# CH32V006-WUI-R1.net
KiCad netlist of a schematic drawn in Altium Designer
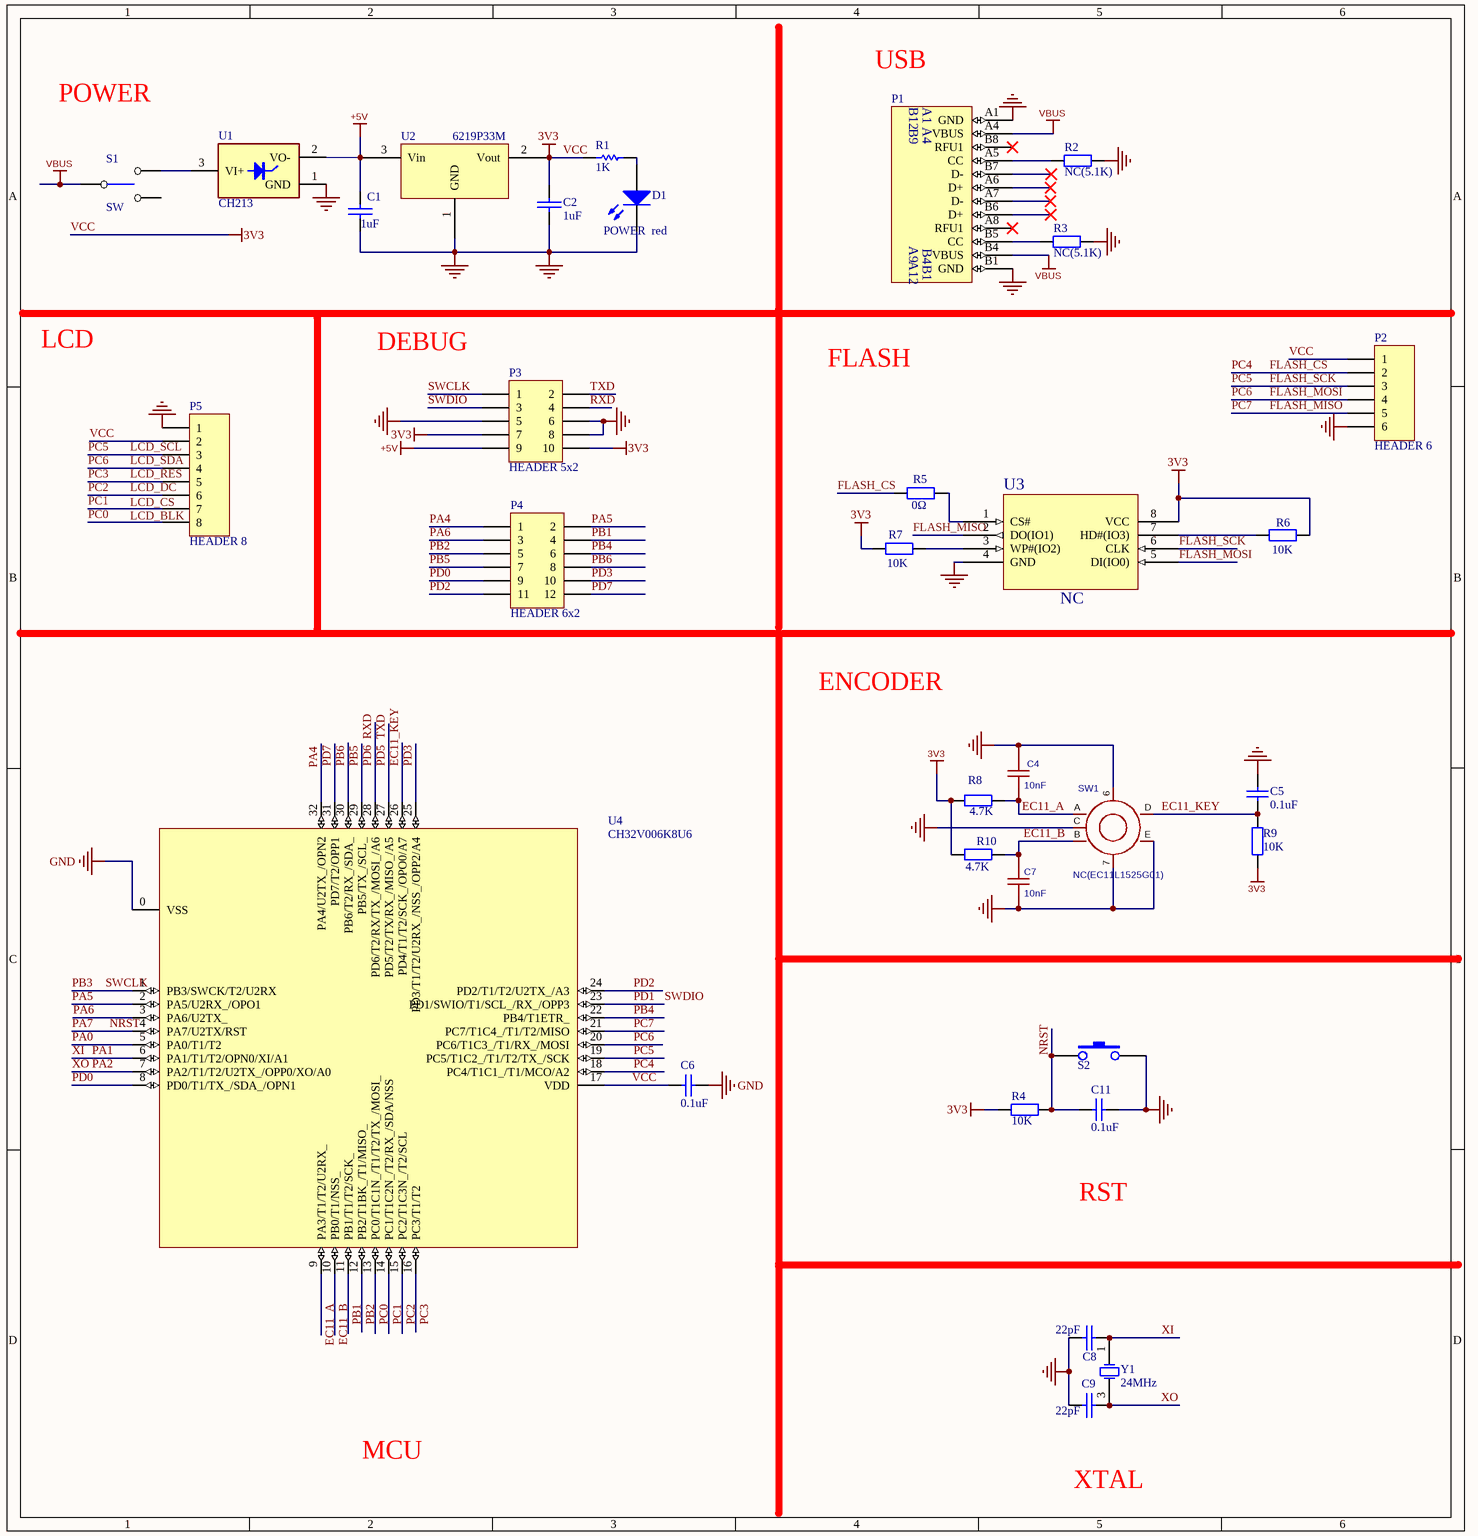
[diagram p0: CH32V006-WUI-R1.SchDoc]

(export (version "E")
  (design (tool "Eeschema 10.0.6"))
  (components
    (comp (ref "C1")
      (value "1uF")
      (footprint "0402_C")
      (description "Capacitor")
      (libsource (lib "*") (part "CAP"))
    )
    (comp (ref "C2")
      (value "1uF")
      (footprint "0402_C")
      (description "Capacitor")
      (libsource (lib "*") (part "CAP"))
    )
    (comp (ref "C4")
      (value "10nF")
      (footprint "0402_C")
      (libsource (lib "altium-import") (part "root_1_CAP_0603_"))
    )
    (comp (ref "C5")
      (value "0.1uF")
      (footprint "0402_C")
      (description "Capacitor")
      (fields (field (name "PUBLISHER") "Altium Limited"))
      (libsource (lib "*") (part "Cap"))
    )
    (comp (ref "C6")
      (value "0.1uF")
      (footprint "0402_C")
      (description "Capacitor")
      (fields (field (name "PUBLISHER") "Altium Limited"))
      (libsource (lib "*") (part "Cap"))
    )
    (comp (ref "C7")
      (value "10nF")
      (footprint "0402_C")
      (libsource (lib "altium-import") (part "root_3_CAP_0603_"))
    )
    (comp (ref "C8")
      (value "22pF")
      (footprint "0402_C")
      (description "Capacitor")
      (libsource (lib "*") (part "CAP"))
    )
    (comp (ref "C9")
      (value "22pF")
      (footprint "0402_C")
      (description "Capacitor")
      (libsource (lib "*") (part "CAP"))
    )
    (comp (ref "C11")
      (value "0.1uF")
      (footprint "0402_C")
      (description "Capacitor")
      (fields (field (name "PUBLISHER") "Altium Limited"))
      (libsource (lib "*") (part "Cap"))
    )
    (comp (ref "D1")
      (value "POWER  red")
      (footprint "0603+")
      (description "Typical INFRARED GaAs LED")
      (fields (field (name "PUBLISHER") "Altium Limited"))
      (libsource (lib "*") (part "LED0"))
    )
    (comp (ref "P1")
      (value "TYPE-C")
      (footprint "TYPE-C-Receptacle-2.0")
      (libsource (lib "*") (part "TYPE-C1"))
    )
    (comp (ref "P2")
      (value "HEADER 6")
      (footprint "SIP6-2.54mm")
      (description "Header, 6-Pin")
      (libsource (lib "wch_sch_others") (part "HEADER 6"))
    )
    (comp (ref "P3")
      (value "HEADER 5x2")
      (footprint "MYPCB:IDC10-2.54mm")
      (description "Header, 5-Pin, Dual row")
      (libsource (lib "wch_sch_others") (part "HEADER 5x2"))
    )
    (comp (ref "P4")
      (value "HEADER 6x2")
      (footprint "MYPCB:IDC12-2.54mm")
      (description "Header, 6-Pin, Dual row")
      (libsource (lib "wch_sch_others") (part "HEADER 6x2"))
    )
    (comp (ref "P5")
      (value "HEADER 8")
      (footprint "SIP8-2.54mm")
      (description "Header, 8-Pin")
      (libsource (lib "wch_sch_others") (part "HEADER 8"))
    )
    (comp (ref "R1")
      (value "1K")
      (footprint "0402")
      (description "Semiconductor Resistor")
      (fields (field (name "PUBLISHER") "Altium Limited"))
      (libsource (lib "*") (part "Res Semi"))
    )
    (comp (ref "R2")
      (value "NC(5.1K)")
      (footprint "0402")
      (description "Resistor")
      (libsource (lib "Miscellaneous Devices") (part "Res2"))
    )
    (comp (ref "R3")
      (value "NC(5.1K)")
      (footprint "0402")
      (description "Resistor")
      (libsource (lib "Miscellaneous Devices") (part "Res2"))
    )
    (comp (ref "R4")
      (value "10K")
      (footprint "0402")
      (description "Resistor")
      (fields (field (name "PUBLISHER") "Altium Limited"))
      (libsource (lib "") (part "Res2_1"))
    )
    (comp (ref "R5")
      (value "0Ω")
      (footprint "0402")
      (description "Resistor")
      (fields (field (name "PUBLISHER") "Altium Limited"))
      (libsource (lib "*") (part "Res2"))
    )
    (comp (ref "R6")
      (value "10K")
      (footprint "0402")
      (description "Resistor")
      (fields (field (name "PUBLISHER") "Altium Limited"))
      (libsource (lib "*") (part "Res2"))
    )
    (comp (ref "R7")
      (value "10K")
      (footprint "0402")
      (description "Resistor")
      (fields (field (name "PUBLISHER") "Altium Limited"))
      (libsource (lib "*") (part "Res2"))
    )
    (comp (ref "R8")
      (value "4.7K")
      (footprint "0402")
      (description "Resistor")
      (fields (field (name "PUBLISHER") "Altium Limited"))
      (libsource (lib "*") (part "Res2"))
    )
    (comp (ref "R9")
      (value "10K")
      (footprint "0402")
      (description "Resistor")
      (fields (field (name "PUBLISHER") "Altium Limited"))
      (libsource (lib "") (part "Res2_2"))
    )
    (comp (ref "R10")
      (value "4.7K")
      (footprint "0402")
      (description "Resistor")
      (fields (field (name "PUBLISHER") "Altium Limited"))
      (libsource (lib "*") (part "Res2"))
    )
    (comp (ref "S1") (value "SW") (footprint "SW1") (libsource (lib "*") (part "SW")))
    (comp (ref "S2") (value "NRST") (footprint "贴片按键") (libsource (lib "*") (part "KEY")))
    (comp (ref "SW1")
      (value "NC(EC11L1525G01)")
      (footprint "SW-TH_ALPS_EC11L1525G01")
      (fields
        (field (name "MANUFACTURER") "ALPSALPINE(阿尔卑斯阿尔派)")
        (field (name "MANUFACTURERPART") "EC11L1525G01")
      )
      (libsource (lib "altium-import") (part "root_3_EC11L1525G01_"))
    )
    (comp (ref "U1")
      (value "CH213")
      (footprint "SOT-23-3")
      (description "Ideal Diode 5V*1A")
      (libsource (lib "CHXXX") (part "CH213E"))
    )
    (comp (ref "U2")
      (value "6219P33M")
      (footprint "SOT-23")
      (libsource (lib "wch_sch_others") (part "6219P33M"))
    )
    (comp (ref "U3")
      (value "NC")
      (footprint "SOIC-8_208mil")
      (libsource (lib "wch_sch_others") (part "W25Q32JV"))
    )
    (comp (ref "U4")
      (value "CH32V006K8U6")
      (footprint "QFN32_4X4")
      (description "RISC-V MCU, 48MHz, ADC/OPA/2*UART/I2C/SPI")
      (libsource (lib "CHXXX(2)") (part "CH32V006K8U6"))
    )
    (comp (ref "Y1")
      (value "24MHz")
      (footprint "XT3225")
      (description "Crystal Oscillator")
      (fields (field (name "PUBLISHER") "Altium Limited"))
      (libsource (lib "*") (part "XTAL"))
    )
  )
  (nets
    (net (code "1") (name "+5V") (class "Default")
      (node (ref "C1") (pin "1") (pinfunction "1_1") (pintype "passive"))
      (node (ref "P3") (pin "9") (pinfunction "9_9") (pintype "passive"))
      (node (ref "U1") (pin "2") (pinfunction "VO-_2") (pintype "power_in"))
      (node (ref "U2") (pin "3") (pinfunction "Vin_3") (pintype "passive"))
    )
    (net (code "2") (name "/EC11_A") (class "Default")
      (node (ref "C4") (pin "1") (pinfunction "1_1") (pintype "passive"))
      (node (ref "R8") (pin "2") (pinfunction "2_2") (pintype "passive"))
      (node (ref "SW1") (pin "A") (pinfunction "A_A") (pintype "passive"))
      (node (ref "U4") (pin "9") (pinfunction "PA3/T1/T2/U2RX__9") (pintype "bidirectional"))
    )
    (net (code "3") (name "/EC11_B") (class "Default")
      (node (ref "C7") (pin "1") (pinfunction "1_1") (pintype "passive"))
      (node (ref "R10") (pin "2") (pinfunction "2_2") (pintype "passive"))
      (node (ref "SW1") (pin "B") (pinfunction "B_B") (pintype "passive"))
      (node (ref "U4") (pin "10") (pinfunction "PB0/T1/NSS__10") (pintype "bidirectional"))
    )
    (net (code "4") (name "/EC11_KEY") (class "Default")
      (node (ref "C5") (pin "2") (pinfunction "2_2") (pintype "passive"))
      (node (ref "R9") (pin "2") (pinfunction "2_2") (pintype "passive"))
      (node (ref "SW1") (pin "D") (pinfunction "D_D") (pintype "passive"))
      (node (ref "U4") (pin "26") (pinfunction "PD4/T1/T2/SCK_/OPO0/A7_26") (pintype "bidirectional"))
    )
    (net (code "5") (name "/FLASH_CS") (class "Default")
      (node (ref "P2") (pin "2") (pinfunction "2_2") (pintype "passive"))
      (node (ref "R5") (pin "1") (pinfunction "1_1") (pintype "passive"))
      (node (ref "U4") (pin "18") (pinfunction "PC4/T1C1_/T1/MCO/A2_18") (pintype "bidirectional"))
    )
    (net (code "6") (name "/FLASH_MISO") (class "Default")
      (node (ref "P2") (pin "5") (pinfunction "5_5") (pintype "passive"))
      (node (ref "U3") (pin "2") (pinfunction "DO(IO1)_2") (pintype "output"))
      (node (ref "U4") (pin "21") (pinfunction "PC7/T1C4_/T1/T2/MISO_21") (pintype "bidirectional"))
    )
    (net (code "7") (name "/FLASH_MOSI") (class "Default")
      (node (ref "P2") (pin "4") (pinfunction "4_4") (pintype "passive"))
      (node (ref "P5") (pin "4") (pinfunction "4_4") (pintype "passive"))
      (node (ref "U3") (pin "5") (pinfunction "DI(IO0)_5") (pintype "input"))
      (node (ref "U4") (pin "20") (pinfunction "PC6/T1C3_/T1/RX_/MOSI_20") (pintype "bidirectional"))
    )
    (net (code "8") (name "/FLASH_SCK") (class "Default")
      (node (ref "P2") (pin "3") (pinfunction "3_3") (pintype "passive"))
      (node (ref "P5") (pin "3") (pinfunction "3_3") (pintype "passive"))
      (node (ref "U3") (pin "6") (pinfunction "CLK_6") (pintype "input"))
      (node (ref "U4") (pin "19") (pinfunction "PC5/T1C2_/T1/T2/TX_/SCK_19") (pintype "bidirectional"))
    )
    (net (code "11") (name "/LCD_DC") (class "Default")
      (node (ref "P5") (pin "6") (pinfunction "6_6") (pintype "passive"))
      (node (ref "U4") (pin "15") (pinfunction "PC2/T1C3N_/T2/SCL_15") (pintype "bidirectional"))
    )
    (net (code "12") (name "/LCD_RES") (class "Default")
      (node (ref "P5") (pin "5") (pinfunction "5_5") (pintype "passive"))
      (node (ref "U4") (pin "16") (pinfunction "PC3/T1/T2_16") (pintype "bidirectional"))
    )
    (net (code "13") (name "/NRST") (class "Default")
      (node (ref "C11") (pin "2") (pinfunction "2_2") (pintype "passive"))
      (node (ref "R4") (pin "1") (pinfunction "1_1") (pintype "passive"))
      (node (ref "S2") (pin "1") (pinfunction "1_1") (pintype "passive"))
      (node (ref "U4") (pin "4") (pinfunction "PA7/U2TX/RST_4") (pintype "bidirectional"))
    )
    (net (code "14") (name "/PA0") (class "Default")
      (node (ref "U4") (pin "5") (pinfunction "PA0/T1/T2_5") (pintype "bidirectional"))
    )
    (net (code "15") (name "/PA1") (class "Default")
      (node (ref "C8") (pin "2") (pinfunction "2_2") (pintype "passive"))
      (node (ref "U4") (pin "6") (pinfunction "PA1/T1/T2/OPN0/XI/A1_6") (pintype "bidirectional"))
      (node (ref "Y1") (pin "1") (pinfunction "OSC1_1") (pintype "passive"))
    )
    (net (code "16") (name "/PA2") (class "Default")
      (node (ref "C9") (pin "2") (pinfunction "2_2") (pintype "passive"))
      (node (ref "U4") (pin "7") (pinfunction "PA2/T1/T2/U2TX_/OPP0/XO/A0_7") (pintype "bidirectional"))
      (node (ref "Y1") (pin "3") (pinfunction "OSC2_3") (pintype "passive"))
    )
    (net (code "17") (name "/PA4") (class "Default")
      (node (ref "P4") (pin "1") (pinfunction "1_1") (pintype "passive"))
      (node (ref "U4") (pin "32") (pinfunction "PA4/U2TX_/OPN2_32") (pintype "bidirectional"))
    )
    (net (code "18") (name "/PA5") (class "Default")
      (node (ref "P4") (pin "2") (pinfunction "2_2") (pintype "passive"))
      (node (ref "U4") (pin "2") (pinfunction "PA5/U2RX_/OPO1_2") (pintype "bidirectional"))
    )
    (net (code "19") (name "/PA6") (class "Default")
      (node (ref "P4") (pin "3") (pinfunction "3_3") (pintype "passive"))
      (node (ref "U4") (pin "3") (pinfunction "PA6/U2TX__3") (pintype "bidirectional"))
    )
    (net (code "20") (name "/PB1") (class "Default")
      (node (ref "P4") (pin "4") (pinfunction "4_4") (pintype "passive"))
      (node (ref "U4") (pin "11") (pinfunction "PB1/T1/T2/SCK__11") (pintype "bidirectional"))
    )
    (net (code "21") (name "/PB2") (class "Default")
      (node (ref "P4") (pin "5") (pinfunction "5_5") (pintype "passive"))
      (node (ref "U4") (pin "12") (pinfunction "PB2/T1BK_/T1/MISO__12") (pintype "bidirectional"))
    )
    (net (code "22") (name "/PB3") (class "Default")
      (node (ref "P3") (pin "1") (pinfunction "1_1") (pintype "passive"))
      (node (ref "U4") (pin "1") (pinfunction "PB3/SWCK/T2/U2RX_1") (pintype "bidirectional"))
    )
    (net (code "23") (name "/PB4") (class "Default")
      (node (ref "P4") (pin "6") (pinfunction "6_6") (pintype "passive"))
      (node (ref "U4") (pin "22") (pinfunction "PB4/T1ETR__22") (pintype "bidirectional"))
    )
    (net (code "24") (name "/PB5") (class "Default")
      (node (ref "P4") (pin "7") (pinfunction "7_7") (pintype "passive"))
      (node (ref "U4") (pin "29") (pinfunction "PB5/TX_/SCL__29") (pintype "bidirectional"))
    )
    (net (code "25") (name "/PB6") (class "Default")
      (node (ref "P4") (pin "8") (pinfunction "8_8") (pintype "passive"))
      (node (ref "U4") (pin "30") (pinfunction "PB6/T2/RX_/SDA__30") (pintype "bidirectional"))
    )
    (net (code "26") (name "/PC0") (class "Default")
      (node (ref "P5") (pin "8") (pinfunction "8_8") (pintype "passive"))
      (node (ref "U4") (pin "13") (pinfunction "PC0/T1C1N_/T1/T2/TX_/MOSI__13") (pintype "bidirectional"))
    )
    (net (code "27") (name "/PC1") (class "Default")
      (node (ref "P5") (pin "7") (pinfunction "7_7") (pintype "passive"))
      (node (ref "U4") (pin "14") (pinfunction "PC1/T1C2N_/T2/RX_/SDA/NSS_14") (pintype "bidirectional"))
    )
    (net (code "28") (name "/PD0") (class "Default")
      (node (ref "P4") (pin "9") (pinfunction "9_9") (pintype "passive"))
      (node (ref "U4") (pin "8") (pinfunction "PD0/T1/TX_/SDA_/OPN1_8") (pintype "bidirectional"))
    )
    (net (code "29") (name "/PD1") (class "Default")
      (node (ref "P3") (pin "3") (pinfunction "3_3") (pintype "passive"))
      (node (ref "U4") (pin "23") (pinfunction "PD1/SWIO/T1/SCL_/RX_/OPP3_23") (pintype "bidirectional"))
    )
    (net (code "30") (name "/PD2") (class "Default")
      (node (ref "P4") (pin "11") (pinfunction "11_11") (pintype "passive"))
      (node (ref "U4") (pin "24") (pinfunction "PD2/T1/T2/U2TX_/A3_24") (pintype "bidirectional"))
    )
    (net (code "31") (name "/PD3") (class "Default")
      (node (ref "P4") (pin "10") (pinfunction "10_10") (pintype "passive"))
      (node (ref "U4") (pin "25") (pinfunction "PD3/T1/T2/U2RX_/NSS_/OPP2/A4_25") (pintype "bidirectional"))
    )
    (net (code "32") (name "/PD5") (class "Default")
      (node (ref "P3") (pin "2") (pinfunction "2_2") (pintype "passive"))
      (node (ref "U4") (pin "27") (pinfunction "PD5/T2/TX/RX_/MISO_/A5_27") (pintype "bidirectional"))
    )
    (net (code "33") (name "/PD6") (class "Default")
      (node (ref "P3") (pin "4") (pinfunction "4_4") (pintype "passive"))
      (node (ref "U4") (pin "28") (pinfunction "PD6/T2/RX/TX_/MOSI_/A6_28") (pintype "bidirectional"))
    )
    (net (code "34") (name "/PD7") (class "Default")
      (node (ref "P4") (pin "12") (pinfunction "12_12") (pintype "passive"))
      (node (ref "U4") (pin "31") (pinfunction "PD7/T2/OPP1_31") (pintype "bidirectional"))
    )
    (net (code "35") (name "3V3") (class "Default")
      (node (ref "C2") (pin "1") (pinfunction "1_1") (pintype "passive"))
      (node (ref "C6") (pin "1") (pinfunction "1_1") (pintype "passive"))
      (node (ref "P2") (pin "1") (pinfunction "1_1") (pintype "passive"))
      (node (ref "P3") (pin "10") (pinfunction "10_10") (pintype "passive"))
      (node (ref "P3") (pin "7") (pinfunction "7_7") (pintype "passive"))
      (node (ref "P5") (pin "2") (pinfunction "2_2") (pintype "passive"))
      (node (ref "R1") (pin "2") (pinfunction "2_2") (pintype "passive"))
      (node (ref "R10") (pin "1") (pinfunction "1_1") (pintype "passive"))
      (node (ref "R4") (pin "2") (pinfunction "2_2") (pintype "passive"))
      (node (ref "R6") (pin "2") (pinfunction "2_2") (pintype "passive"))
      (node (ref "R7") (pin "1") (pinfunction "1_1") (pintype "passive"))
      (node (ref "R8") (pin "1") (pinfunction "1_1") (pintype "passive"))
      (node (ref "R9") (pin "1") (pinfunction "1_1") (pintype "passive"))
      (node (ref "U2") (pin "2") (pinfunction "Vout_2") (pintype "passive"))
      (node (ref "U3") (pin "8") (pinfunction "VCC_8") (pintype "power_in"))
      (node (ref "U4") (pin "17") (pinfunction "VDD_17") (pintype "power_in"))
    )
    (net (code "36") (name "GND") (class "Default")
      (node (ref "C1") (pin "2") (pinfunction "2_2") (pintype "passive"))
      (node (ref "C11") (pin "1") (pinfunction "1_1") (pintype "passive"))
      (node (ref "C2") (pin "2") (pinfunction "2_2") (pintype "passive"))
      (node (ref "C4") (pin "2") (pinfunction "2_2") (pintype "passive"))
      (node (ref "C5") (pin "1") (pinfunction "1_1") (pintype "passive"))
      (node (ref "C6") (pin "2") (pinfunction "2_2") (pintype "passive"))
      (node (ref "C7") (pin "2") (pinfunction "2_2") (pintype "passive"))
      (node (ref "C8") (pin "1") (pinfunction "1_1") (pintype "passive"))
      (node (ref "C9") (pin "1") (pinfunction "1_1") (pintype "passive"))
      (node (ref "D1") (pin "2") (pinfunction "K_2") (pintype "passive"))
      (node (ref "P1") (pin "A1") (pinfunction "GND_A1") (pintype "bidirectional"))
      (node (ref "P1") (pin "B1") (pinfunction "GND_B1") (pintype "bidirectional"))
      (node (ref "P2") (pin "6") (pinfunction "6_6") (pintype "passive"))
      (node (ref "P3") (pin "5") (pinfunction "5_5") (pintype "passive"))
      (node (ref "P3") (pin "6") (pinfunction "6_6") (pintype "passive"))
      (node (ref "P3") (pin "8") (pinfunction "8_8") (pintype "passive"))
      (node (ref "P5") (pin "1") (pinfunction "1_1") (pintype "passive"))
      (node (ref "R2") (pin "2") (pinfunction "2_2") (pintype "passive"))
      (node (ref "R3") (pin "2") (pinfunction "2_2") (pintype "passive"))
      (node (ref "S2") (pin "2") (pinfunction "2_2") (pintype "passive"))
      (node (ref "SW1") (pin "6") (pinfunction "EH_6") (pintype "passive"))
      (node (ref "SW1") (pin "7") (pinfunction "EH_7") (pintype "passive"))
      (node (ref "SW1") (pin "C") (pinfunction "C_C") (pintype "passive"))
      (node (ref "SW1") (pin "E") (pinfunction "E_E") (pintype "passive"))
      (node (ref "U1") (pin "1") (pinfunction "GND_1") (pintype "power_in"))
      (node (ref "U2") (pin "1") (pinfunction "GND_1") (pintype "passive"))
      (node (ref "U3") (pin "4") (pinfunction "GND_4") (pintype "power_in"))
      (node (ref "U4") (pin "0") (pinfunction "VSS_0") (pintype "power_in"))
    )
    (net (code "37") (name "Net-(D1-A)") (class "Default")
      (node (ref "D1") (pin "1") (pinfunction "A_1") (pintype "passive"))
      (node (ref "R1") (pin "1") (pinfunction "1_1") (pintype "passive"))
    )
    (net (code "38") (name "Net-(P1-CC-PadA5)") (class "Default")
      (node (ref "P1") (pin "A5") (pinfunction "CC_A5") (pintype "bidirectional"))
      (node (ref "R2") (pin "1") (pinfunction "1_1") (pintype "passive"))
    )
    (net (code "39") (name "Net-(P1-CC-PadB5)") (class "Default")
      (node (ref "P1") (pin "B5") (pinfunction "CC_B5") (pintype "bidirectional"))
      (node (ref "R3") (pin "1") (pinfunction "1_1") (pintype "passive"))
    )
    (net (code "40") (name "Net-(U1-VI+)") (class "Default")
      (node (ref "S1") (pin "3") (pinfunction "3_3") (pintype "passive"))
      (node (ref "U1") (pin "3") (pinfunction "VI+_3") (pintype "power_in"))
    )
    (net (code "41") (name "Net-(U3-CS#)") (class "Default")
      (node (ref "R5") (pin "2") (pinfunction "2_2") (pintype "passive"))
      (node (ref "U3") (pin "1") (pinfunction "CS#_1") (pintype "input"))
    )
    (net (code "42") (name "Net-(U3-HD#(IO3))") (class "Default")
      (node (ref "R6") (pin "1") (pinfunction "1_1") (pintype "passive"))
      (node (ref "U3") (pin "7") (pinfunction "HD#(IO3)_7") (pintype "power_in"))
    )
    (net (code "43") (name "Net-(U3-WP#(IO2))") (class "Default")
      (node (ref "R7") (pin "2") (pinfunction "2_2") (pintype "passive"))
      (node (ref "U3") (pin "3") (pinfunction "WP#(IO2)_3") (pintype "input"))
    )
    (net (code "44") (name "VBUS") (class "Default")
      (node (ref "P1") (pin "A4") (pinfunction "VBUS_A4") (pintype "bidirectional"))
      (node (ref "P1") (pin "B4") (pinfunction "VBUS_B4") (pintype "bidirectional"))
      (node (ref "S1") (pin "1") (pinfunction "1_1") (pintype "passive"))
    )
    (net (code "45") (name "unconnected-(P1-D+-PadA6)") (class "Default")
      (node (ref "P1") (pin "A6") (pinfunction "D+_A6") (pintype "bidirectional+no_connect"))
    )
    (net (code "46") (name "unconnected-(P1-D+-PadB6)") (class "Default")
      (node (ref "P1") (pin "B6") (pinfunction "D+_B6") (pintype "bidirectional+no_connect"))
    )
    (net (code "47") (name "unconnected-(P1-D--PadA7)") (class "Default")
      (node (ref "P1") (pin "A7") (pinfunction "D-_A7") (pintype "bidirectional+no_connect"))
    )
    (net (code "48") (name "unconnected-(P1-D--PadB7)") (class "Default")
      (node (ref "P1") (pin "B7") (pinfunction "D-_B7") (pintype "bidirectional+no_connect"))
    )
    (net (code "49") (name "unconnected-(P1-RFU1-PadA8)") (class "Default")
      (node (ref "P1") (pin "A8") (pinfunction "RFU1_A8") (pintype "bidirectional+no_connect"))
    )
    (net (code "50") (name "unconnected-(P1-RFU1-PadB8)") (class "Default")
      (node (ref "P1") (pin "B8") (pinfunction "RFU1_B8") (pintype "bidirectional+no_connect"))
    )
    (net (code "51") (name "unconnected-(S1-Pad2)") (class "Default")
      (node (ref "S1") (pin "2") (pinfunction "2_2") (pintype "passive"))
    )
  )
)
